# SparkFun_RTK_Facet_-_Display_SD.net
KiCad netlist of a schematic drawn in EAGLE
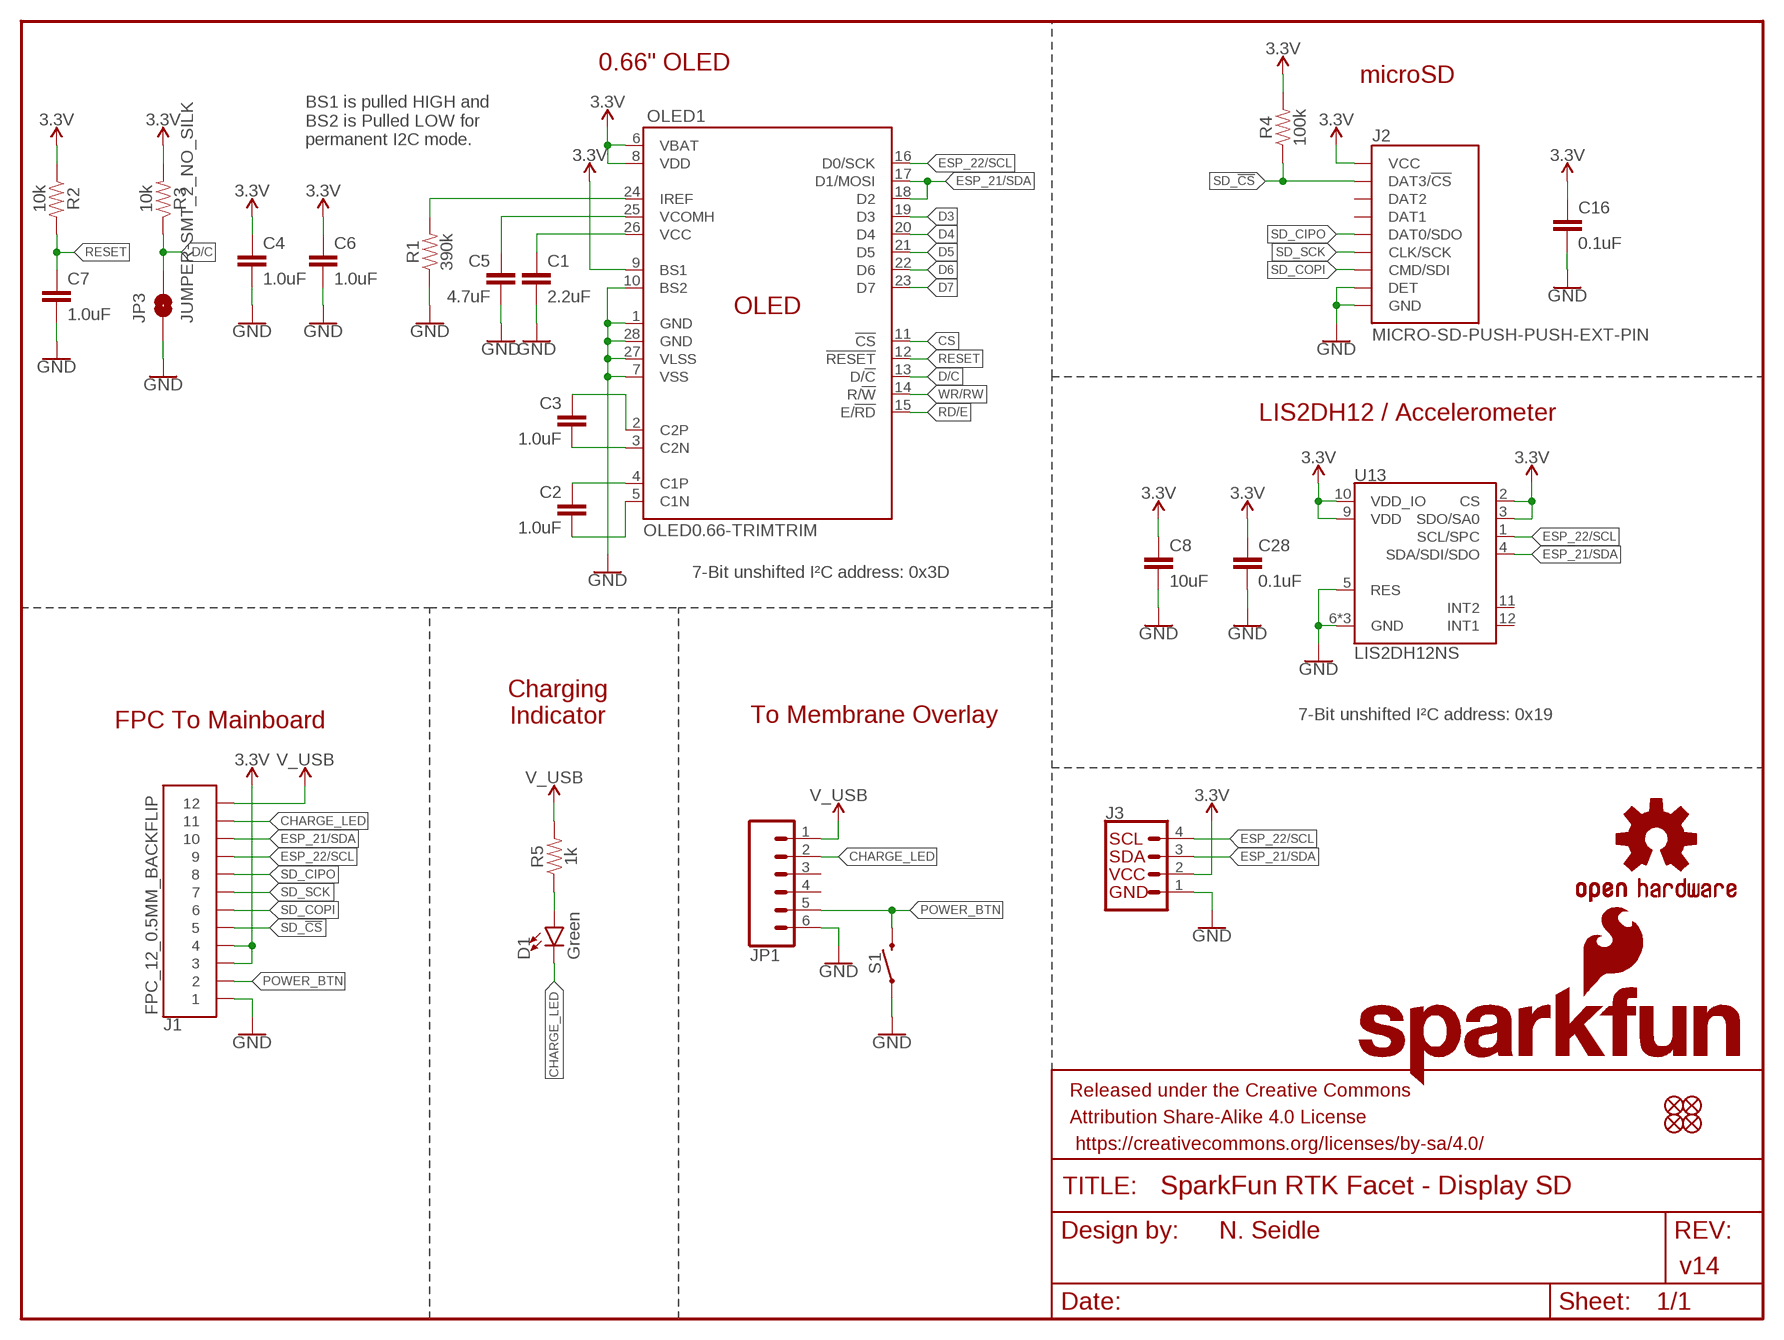
[diagram p0: schematic, sheet 1]

(export (version "E")
  (design (tool "Eeschema 10.0.6"))
  (components
    (comp (ref "C1")
      (value "2.2uF")
      (footprint "eagle-import:0805")
      (libsource (lib "eagle-import") (part "2.2UF-0805-25V-(+80/-20%)"))
    )
    (comp (ref "C2")
      (value "1.0uF")
      (footprint "eagle-import:0805")
      (libsource (lib "eagle-import") (part "1.0UF-0805-25V-10%"))
    )
    (comp (ref "C3")
      (value "1.0uF")
      (footprint "eagle-import:0805")
      (libsource (lib "eagle-import") (part "1.0UF-0805-25V-10%"))
    )
    (comp (ref "C4")
      (value "1.0uF")
      (footprint "eagle-import:0603")
      (libsource (lib "eagle-import") (part "1.0UF-0603-16V-10%"))
    )
    (comp (ref "C5")
      (value "4.7uF")
      (footprint "eagle-import:1206")
      (libsource (lib "eagle-import") (part "4.7UF-1206-16V-(+80/-20%)"))
    )
    (comp (ref "C6")
      (value "1.0uF")
      (footprint "eagle-import:0603")
      (libsource (lib "eagle-import") (part "1.0UF-0603-16V-10%"))
    )
    (comp (ref "C7")
      (value "1.0uF")
      (footprint "eagle-import:0603")
      (libsource (lib "eagle-import") (part "1.0UF-0603-16V-10%"))
    )
    (comp (ref "C8")
      (value "10uF")
      (footprint "eagle-import:0603")
      (libsource (lib "eagle-import") (part "10UF-0603-6.3V-20%"))
    )
    (comp (ref "C16")
      (value "0.1uF")
      (footprint "eagle-import:0603")
      (libsource (lib "eagle-import") (part "0.1UF-0603-25V-(+80/-20%)"))
    )
    (comp (ref "C28")
      (value "0.1uF")
      (footprint "eagle-import:0603")
      (libsource (lib "eagle-import") (part "0.1UF-0603-25V-(+80/-20%)"))
    )
    (comp (ref "D1")
      (value "Green")
      (footprint "eagle-import:LED-1206-BOTTOM")
      (libsource (lib "eagle-import") (part "LED-GREEN1206-BOTTOM"))
    )
    (comp (ref "FID1")
      (value "FIDUCIAL1X2")
      (footprint "eagle-import:FIDUCIAL-1X2")
      (libsource (lib "eagle-import") (part "FIDUCIAL1X2"))
    )
    (comp (ref "FID2")
      (value "FIDUCIAL1X2")
      (footprint "eagle-import:FIDUCIAL-1X2")
      (libsource (lib "eagle-import") (part "FIDUCIAL1X2"))
    )
    (comp (ref "FID3")
      (value "FIDUCIAL1X2")
      (footprint "eagle-import:FIDUCIAL-1X2")
      (libsource (lib "eagle-import") (part "FIDUCIAL1X2"))
    )
    (comp (ref "FID4")
      (value "FIDUCIAL1X2")
      (footprint "eagle-import:FIDUCIAL-1X2")
      (libsource (lib "eagle-import") (part "FIDUCIAL1X2"))
    )
    (comp (ref "FRAME1")
      (value "FRAME-LETTER")
      (footprint "eagle-import:CREATIVE_COMMONS")
      (libsource (lib "eagle-import") (part "FRAME-LETTER"))
    )
    (comp (ref "J1")
      (value "FPC_12_0.5MM_BACKFLIP")
      (footprint "eagle-import:FPC_12_DOUBLESIDED_BACKFLIP")
      (libsource (lib "eagle-import") (part "FPC_12_0.5MM_BACKFLIP"))
    )
    (comp (ref "J2")
      (value "MICRO-SD-PUSH-PUSH-EXT-PIN")
      (footprint "eagle-import:MICROSD-EXTERNALPIN")
      (libsource (lib "eagle-import") (part "MICRO-SD-PUSH-PUSH-EXT-PIN"))
    )
    (comp (ref "J3")
      (value "I2C_STANDARD_NO_SILK")
      (footprint "eagle-import:1X04_NO_SILK")
      (libsource (lib "eagle-import") (part "I2C_STANDARD_NO_SILK"))
    )
    (comp (ref "JP1")
      (value "CONN_061MM-LIF")
      (footprint "eagle-import:FPC_6_1MM-LIF")
      (libsource (lib "eagle-import") (part "CONN_061MM-LIF"))
    )
    (comp (ref "JP3")
      (value "JUMPER-SMT_2_NO_SILK")
      (footprint "eagle-import:SMT-JUMPER_2_NO_SILK")
      (libsource (lib "eagle-import") (part "JUMPER-SMT_2_NO_SILK"))
    )
    (comp (ref "LOGO3")
      (value "OSHW-LOGOMINI")
      (footprint "eagle-import:OSHW-LOGO-MINI")
      (libsource (lib "eagle-import") (part "OSHW-LOGOMINI"))
    )
    (comp (ref "LOGO5")
      (value "SFE_LOGO_NAME_FLAME8_MM")
      (footprint "eagle-import:SFE_LOGO_NAME_FLAME_8MM")
      (libsource (lib "eagle-import") (part "SFE_LOGO_NAME_FLAME8_MM"))
    )
    (comp (ref "OLED1")
      (value "OLED0.66-TRIMTRIM")
      (footprint "eagle-import:OLED-0.66-64X48-TRIM")
      (libsource (lib "eagle-import") (part "OLED0.66-TRIMTRIM"))
    )
    (comp (ref "R1")
      (value "390k")
      (footprint "eagle-import:0603")
      (libsource (lib "eagle-import") (part "390KOHM-0603-1/10W-1%"))
    )
    (comp (ref "R2")
      (value "10k")
      (footprint "eagle-import:0603")
      (libsource (lib "eagle-import") (part "10KOHM-0603-1/10W-1%"))
    )
    (comp (ref "R3")
      (value "10k")
      (footprint "eagle-import:0603")
      (libsource (lib "eagle-import") (part "10KOHM-0603-1/10W-1%"))
    )
    (comp (ref "R4")
      (value "100k")
      (footprint "eagle-import:0603")
      (libsource (lib "eagle-import") (part "100KOHM-0603-1/10W-1%"))
    )
    (comp (ref "R5")
      (value "1k")
      (footprint "eagle-import:0603")
      (libsource (lib "eagle-import") (part "1KOHM-0603-1/10W-1%"))
    )
    (comp (ref "S1")
      (value "MOMENTARY-SWITCH-SPST-SMD-5.2MM-TALL")
      (footprint "eagle-import:TACTILE_SWITCH_SMD_5.2MM")
      (libsource (lib "eagle-import") (part "MOMENTARY-SWITCH-SPST-SMD-5.2MM-TALL"))
    )
    (comp (ref "U13")
      (value "LIS2DH12NS")
      (footprint "eagle-import:LGA-12-LISDH12-NOSILK")
      (libsource (lib "eagle-import") (part "LIS2DH12NS"))
    )
  )
  (nets
    (net (code "1") (name "/SD_~{CS}") (class "Default")
      (node (ref "J1") (pin "5") (pinfunction "5_5") (pintype "bidirectional"))
      (node (ref "J2") (pin "2") (pinfunction "DAT3/~{CS}_2") (pintype "bidirectional"))
      (node (ref "R4") (pin "1") (pinfunction "1_1") (pintype "passive"))
    )
    (net (code "2") (name "3.3V") (class "Default")
      (node (ref "C16") (pin "1") (pinfunction "1_1") (pintype "passive"))
      (node (ref "C28") (pin "1") (pinfunction "1_1") (pintype "passive"))
      (node (ref "C4") (pin "1") (pinfunction "1_1") (pintype "passive"))
      (node (ref "C6") (pin "1") (pinfunction "1_1") (pintype "passive"))
      (node (ref "C8") (pin "1") (pinfunction "1_1") (pintype "passive"))
      (node (ref "J1") (pin "3") (pinfunction "3_3") (pintype "bidirectional"))
      (node (ref "J1") (pin "4") (pinfunction "4_4") (pintype "bidirectional"))
      (node (ref "J2") (pin "4") (pinfunction "VCC_4") (pintype "bidirectional"))
      (node (ref "J3") (pin "2") (pinfunction "2_2") (pintype "power_in"))
      (node (ref "OLED1") (pin "6") (pinfunction "VBAT_6") (pintype "bidirectional"))
      (node (ref "OLED1") (pin "8") (pinfunction "VDD_8") (pintype "bidirectional"))
      (node (ref "OLED1") (pin "9") (pinfunction "BS1_9") (pintype "bidirectional"))
      (node (ref "R2") (pin "1") (pinfunction "1_1") (pintype "passive"))
      (node (ref "R3") (pin "2") (pinfunction "2_2") (pintype "passive"))
      (node (ref "R4") (pin "2") (pinfunction "2_2") (pintype "passive"))
      (node (ref "U13") (pin "10") (pinfunction "VDD_IO_10") (pintype "bidirectional"))
      (node (ref "U13") (pin "2") (pinfunction "CS_2") (pintype "bidirectional"))
      (node (ref "U13") (pin "3") (pinfunction "SDO/SA0_3") (pintype "bidirectional"))
      (node (ref "U13") (pin "9") (pinfunction "VDD_9") (pintype "bidirectional"))
    )
    (net (code "3") (name "CHARGE_LED") (class "Default")
      (node (ref "D1") (pin "C") (pinfunction "C_C") (pintype "passive"))
      (node (ref "J1") (pin "11") (pinfunction "11_11") (pintype "bidirectional"))
      (node (ref "JP1") (pin "2") (pinfunction "2_2") (pintype "passive"))
    )
    (net (code "4") (name "CS") (class "Default")
      (node (ref "OLED1") (pin "11") (pinfunction "~{CS}_11") (pintype "bidirectional"))
    )
    (net (code "5") (name "D3") (class "Default")
      (node (ref "OLED1") (pin "19") (pinfunction "D3_19") (pintype "bidirectional"))
    )
    (net (code "6") (name "D4") (class "Default")
      (node (ref "OLED1") (pin "20") (pinfunction "D4_20") (pintype "bidirectional"))
    )
    (net (code "7") (name "D5") (class "Default")
      (node (ref "OLED1") (pin "21") (pinfunction "D5_21") (pintype "bidirectional"))
    )
    (net (code "8") (name "D6") (class "Default")
      (node (ref "OLED1") (pin "22") (pinfunction "D6_22") (pintype "bidirectional"))
    )
    (net (code "9") (name "D7") (class "Default")
      (node (ref "OLED1") (pin "23") (pinfunction "D7_23") (pintype "bidirectional"))
    )
    (net (code "10") (name "D{slash}C") (class "Default")
      (node (ref "JP3") (pin "2") (pinfunction "2_2") (pintype "passive"))
      (node (ref "OLED1") (pin "13") (pinfunction "D/~{C}_13") (pintype "bidirectional"))
      (node (ref "R3") (pin "1") (pinfunction "1_1") (pintype "passive"))
    )
    (net (code "11") (name "ESP_21{slash}SDA") (class "Default")
      (node (ref "J1") (pin "10") (pinfunction "10_10") (pintype "bidirectional"))
      (node (ref "J3") (pin "3") (pinfunction "3_3") (pintype "passive"))
      (node (ref "OLED1") (pin "17") (pinfunction "D1/MOSI_17") (pintype "bidirectional"))
      (node (ref "OLED1") (pin "18") (pinfunction "D2_18") (pintype "bidirectional"))
      (node (ref "U13") (pin "4") (pinfunction "SDA/SDI/SDO_4") (pintype "bidirectional"))
    )
    (net (code "12") (name "ESP_22{slash}SCL") (class "Default")
      (node (ref "J1") (pin "9") (pinfunction "9_9") (pintype "bidirectional"))
      (node (ref "J3") (pin "4") (pinfunction "4_4") (pintype "passive"))
      (node (ref "OLED1") (pin "16") (pinfunction "D0/SCK_16") (pintype "bidirectional"))
      (node (ref "U13") (pin "1") (pinfunction "SCL/SPC_1") (pintype "bidirectional"))
    )
    (net (code "13") (name "GND") (class "Default")
      (node (ref "C1") (pin "2") (pinfunction "2_2") (pintype "passive"))
      (node (ref "C16") (pin "2") (pinfunction "2_2") (pintype "passive"))
      (node (ref "C28") (pin "2") (pinfunction "2_2") (pintype "passive"))
      (node (ref "C4") (pin "2") (pinfunction "2_2") (pintype "passive"))
      (node (ref "C5") (pin "2") (pinfunction "2_2") (pintype "passive"))
      (node (ref "C6") (pin "2") (pinfunction "2_2") (pintype "passive"))
      (node (ref "C7") (pin "2") (pinfunction "2_2") (pintype "passive"))
      (node (ref "C8") (pin "2") (pinfunction "2_2") (pintype "passive"))
      (node (ref "J1") (pin "1") (pinfunction "1_1") (pintype "bidirectional"))
      (node (ref "J2") (pin "10") (pinfunction "GND_10") (pintype "bidirectional"))
      (node (ref "J2") (pin "11") (pinfunction "GND_11") (pintype "bidirectional"))
      (node (ref "J2") (pin "12") (pinfunction "GND_12") (pintype "bidirectional"))
      (node (ref "J2") (pin "13") (pinfunction "GND_13") (pintype "bidirectional"))
      (node (ref "J2") (pin "6") (pinfunction "GND_6") (pintype "bidirectional"))
      (node (ref "J2") (pin "9") (pinfunction "DET_9") (pintype "bidirectional"))
      (node (ref "J3") (pin "1") (pinfunction "1_1") (pintype "power_in"))
      (node (ref "JP1") (pin "6") (pinfunction "6_6") (pintype "passive"))
      (node (ref "JP3") (pin "1") (pinfunction "1_1") (pintype "passive"))
      (node (ref "OLED1") (pin "1") (pinfunction "GND_1") (pintype "bidirectional"))
      (node (ref "OLED1") (pin "10") (pinfunction "BS2_10") (pintype "bidirectional"))
      (node (ref "OLED1") (pin "27") (pinfunction "VLSS_27") (pintype "bidirectional"))
      (node (ref "OLED1") (pin "28") (pinfunction "GND_28") (pintype "bidirectional"))
      (node (ref "OLED1") (pin "7") (pinfunction "VSS_7") (pintype "bidirectional"))
      (node (ref "R1") (pin "1") (pinfunction "1_1") (pintype "passive"))
      (node (ref "S1") (pin "1") (pinfunction "1_1") (pintype "passive"))
      (node (ref "U13") (pin "5") (pinfunction "RES_5") (pintype "bidirectional"))
      (node (ref "U13") (pin "6") (pinfunction "GND_6") (pintype "bidirectional"))
      (node (ref "U13") (pin "7") (pinfunction "GND_7") (pintype "bidirectional"))
      (node (ref "U13") (pin "8") (pinfunction "GND_8") (pintype "bidirectional"))
    )
    (net (code "14") (name "Net-(D1-PadA)") (class "Default")
      (node (ref "D1") (pin "A") (pinfunction "A_A") (pintype "passive"))
      (node (ref "R5") (pin "1") (pinfunction "1_1") (pintype "passive"))
    )
    (net (code "15") (name "Net-(OLED1-C1N)") (class "Default")
      (node (ref "C2") (pin "2") (pinfunction "2_2") (pintype "passive"))
      (node (ref "OLED1") (pin "5") (pinfunction "C1N_5") (pintype "bidirectional"))
    )
    (net (code "16") (name "Net-(OLED1-C1P)") (class "Default")
      (node (ref "C2") (pin "1") (pinfunction "1_1") (pintype "passive"))
      (node (ref "OLED1") (pin "4") (pinfunction "C1P_4") (pintype "bidirectional"))
    )
    (net (code "17") (name "Net-(OLED1-C2N)") (class "Default")
      (node (ref "C3") (pin "2") (pinfunction "2_2") (pintype "passive"))
      (node (ref "OLED1") (pin "3") (pinfunction "C2N_3") (pintype "bidirectional"))
    )
    (net (code "18") (name "Net-(OLED1-C2P)") (class "Default")
      (node (ref "C3") (pin "1") (pinfunction "1_1") (pintype "passive"))
      (node (ref "OLED1") (pin "2") (pinfunction "C2P_2") (pintype "bidirectional"))
    )
    (net (code "19") (name "Net-(OLED1-IREF)") (class "Default")
      (node (ref "OLED1") (pin "24") (pinfunction "IREF_24") (pintype "bidirectional"))
      (node (ref "R1") (pin "2") (pinfunction "2_2") (pintype "passive"))
    )
    (net (code "20") (name "Net-(OLED1-VCC)") (class "Default")
      (node (ref "C1") (pin "1") (pinfunction "1_1") (pintype "passive"))
      (node (ref "OLED1") (pin "26") (pinfunction "VCC_26") (pintype "bidirectional"))
    )
    (net (code "21") (name "Net-(OLED1-VCOMH)") (class "Default")
      (node (ref "C5") (pin "1") (pinfunction "1_1") (pintype "passive"))
      (node (ref "OLED1") (pin "25") (pinfunction "VCOMH_25") (pintype "bidirectional"))
    )
    (net (code "22") (name "POWER_BTN") (class "Default")
      (node (ref "J1") (pin "2") (pinfunction "2_2") (pintype "bidirectional"))
      (node (ref "JP1") (pin "5") (pinfunction "5_5") (pintype "passive"))
      (node (ref "S1") (pin "3") (pinfunction "2_3") (pintype "passive"))
    )
    (net (code "23") (name "RD{slash}E") (class "Default")
      (node (ref "OLED1") (pin "15") (pinfunction "E/~{RD}_15") (pintype "bidirectional"))
    )
    (net (code "24") (name "RESET") (class "Default")
      (node (ref "C7") (pin "1") (pinfunction "1_1") (pintype "passive"))
      (node (ref "OLED1") (pin "12") (pinfunction "~{RESET}_12") (pintype "bidirectional"))
      (node (ref "R2") (pin "2") (pinfunction "2_2") (pintype "passive"))
    )
    (net (code "25") (name "SD_CIPO") (class "Default")
      (node (ref "J1") (pin "8") (pinfunction "8_8") (pintype "bidirectional"))
      (node (ref "J2") (pin "7") (pinfunction "DAT0/SDO_7") (pintype "bidirectional"))
    )
    (net (code "26") (name "SD_COPI") (class "Default")
      (node (ref "J1") (pin "6") (pinfunction "6_6") (pintype "bidirectional"))
      (node (ref "J2") (pin "3") (pinfunction "CMD/SDI_3") (pintype "bidirectional"))
    )
    (net (code "27") (name "SD_SCK") (class "Default")
      (node (ref "J1") (pin "7") (pinfunction "7_7") (pintype "bidirectional"))
      (node (ref "J2") (pin "5") (pinfunction "CLK/SCK_5") (pintype "bidirectional"))
    )
    (net (code "28") (name "V_USB") (class "Default")
      (node (ref "J1") (pin "12") (pinfunction "12_12") (pintype "bidirectional"))
      (node (ref "JP1") (pin "1") (pinfunction "1_1") (pintype "passive"))
      (node (ref "R5") (pin "2") (pinfunction "2_2") (pintype "passive"))
    )
    (net (code "29") (name "WR{slash}RW") (class "Default")
      (node (ref "OLED1") (pin "14") (pinfunction "R/~{W}_14") (pintype "bidirectional"))
    )
    (net (code "30") (name "unconnected-(J2-DAT1-Pad8)") (class "Default")
      (node (ref "J2") (pin "8") (pinfunction "DAT1_8") (pintype "bidirectional"))
    )
    (net (code "31") (name "unconnected-(J2-DAT2-Pad1)") (class "Default")
      (node (ref "J2") (pin "1") (pinfunction "DAT2_1") (pintype "bidirectional"))
    )
    (net (code "32") (name "unconnected-(JP1-Pad3)") (class "Default")
      (node (ref "JP1") (pin "3") (pinfunction "3_3") (pintype "passive"))
    )
    (net (code "33") (name "unconnected-(JP1-Pad4)") (class "Default")
      (node (ref "JP1") (pin "4") (pinfunction "4_4") (pintype "passive"))
    )
    (net (code "34") (name "unconnected-(U13-INT1-Pad12)") (class "Default")
      (node (ref "U13") (pin "12") (pinfunction "INT1_12") (pintype "bidirectional"))
    )
    (net (code "35") (name "unconnected-(U13-INT2-Pad11)") (class "Default")
      (node (ref "U13") (pin "11") (pinfunction "INT2_11") (pintype "bidirectional"))
    )
  )
)
